# zOUT_fp_00a.net
KiCad netlist of a schematic drawn in EAGLE
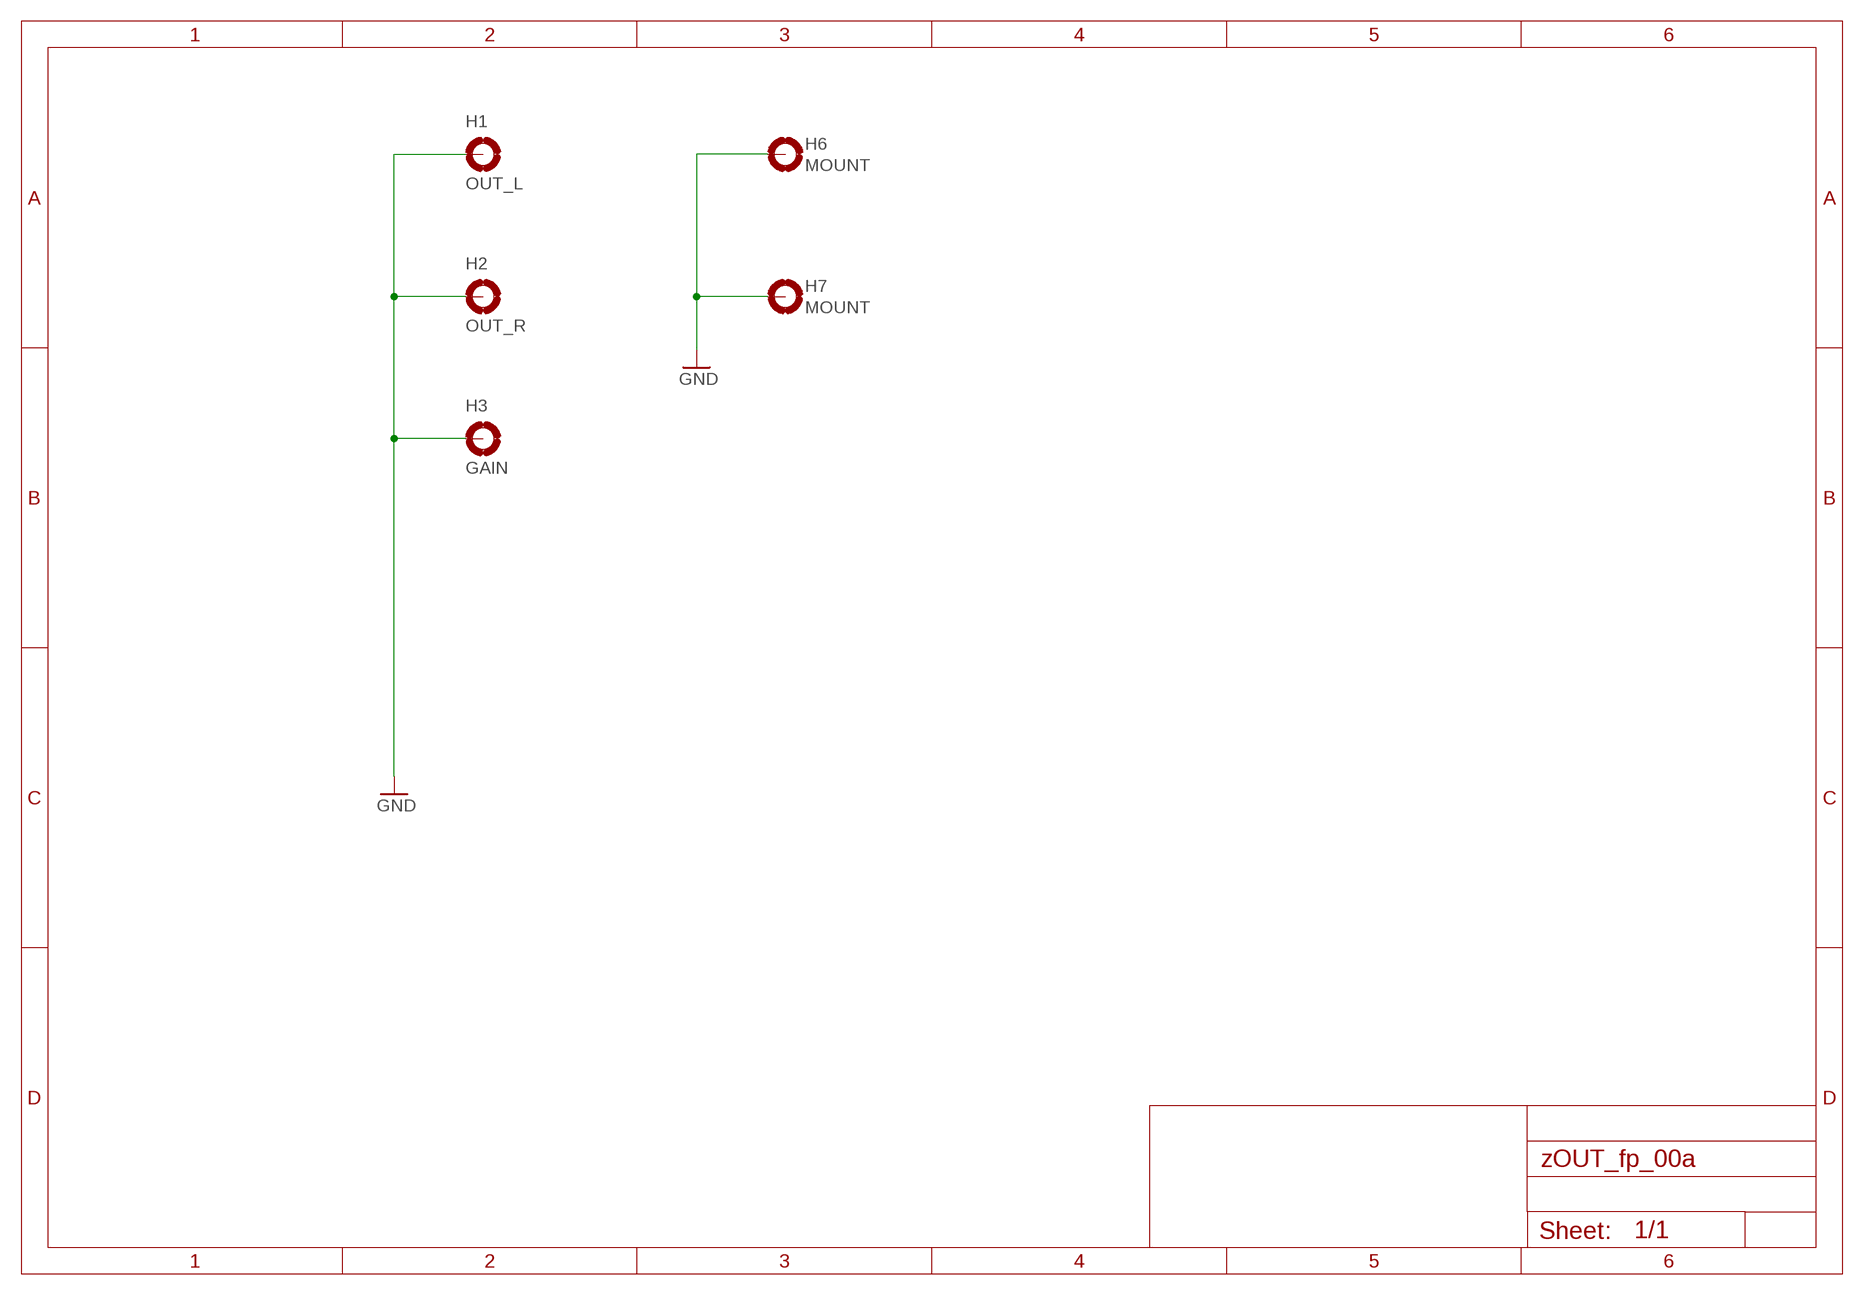
[diagram p0: schematic, sheet 1]

(export (version "E")
  (design (tool "Eeschema 10.0.6"))
  (components
    (comp (ref "H1")
      (value "OUT_L")
      (footprint "eagle-import:6,223-PAD")
      (libsource (lib "eagle-import") (part "MOUNT-PAD-ROUND6.223"))
    )
    (comp (ref "H2")
      (value "OUT_R")
      (footprint "eagle-import:6,223-PAD")
      (libsource (lib "eagle-import") (part "MOUNT-PAD-ROUND6.223"))
    )
    (comp (ref "H3")
      (value "GAIN")
      (footprint "eagle-import:7.112-PAD")
      (libsource (lib "eagle-import") (part "MOUNT-PAD-ROUND7.112"))
    )
    (comp (ref "H6")
      (value "MOUNT")
      (footprint "eagle-import:3,2-PAD_L")
      (libsource (lib "eagle-import") (part "MOUNT-PAD-LONG3.2"))
    )
    (comp (ref "H7")
      (value "MOUNT")
      (footprint "eagle-import:3,2-PAD_L")
      (libsource (lib "eagle-import") (part "MOUNT-PAD-LONG3.2"))
    )
  )
  (nets
    (net (code "1") (name "GND") (class "Default")
      (node (ref "H1") (pin "B6,223") (pinfunction "MOUNT_B6,223") (pintype "passive"))
      (node (ref "H2") (pin "B6,223") (pinfunction "MOUNT_B6,223") (pintype "passive"))
      (node (ref "H3") (pin "B4,5") (pinfunction "MOUNT_B4,5") (pintype "passive"))
      (node (ref "H6") (pin "B3,2") (pinfunction "MOUNT_B3,2") (pintype "passive"))
      (node (ref "H7") (pin "B3,2") (pinfunction "MOUNT_B3,2") (pintype "passive"))
    )
  )
)
